# vacuum_gripper_v1.net
KiCad netlist of a schematic drawn in EAGLE
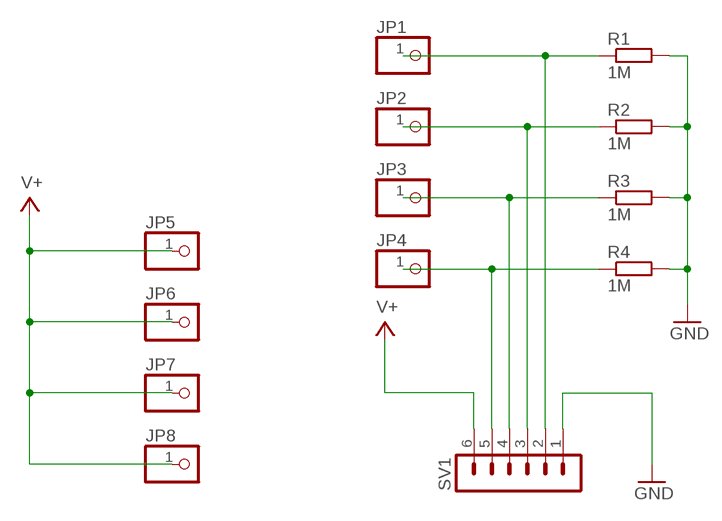
[diagram p0: schematic, sheet 1]

(export (version "E")
  (design (tool "Eeschema 10.0.6"))
  (components
    (comp (ref "JP1")
      (value "PINHD-1X1")
      (footprint "eagle-import:1X01")
      (libsource (lib "eagle-import") (part "PINHD-1X1"))
    )
    (comp (ref "JP2")
      (value "PINHD-1X1")
      (footprint "eagle-import:1X01")
      (libsource (lib "eagle-import") (part "PINHD-1X1"))
    )
    (comp (ref "JP3")
      (value "PINHD-1X1")
      (footprint "eagle-import:1X01")
      (libsource (lib "eagle-import") (part "PINHD-1X1"))
    )
    (comp (ref "JP4")
      (value "PINHD-1X1")
      (footprint "eagle-import:1X01")
      (libsource (lib "eagle-import") (part "PINHD-1X1"))
    )
    (comp (ref "JP5")
      (value "PINHD-1X1")
      (footprint "eagle-import:1X01")
      (libsource (lib "eagle-import") (part "PINHD-1X1"))
    )
    (comp (ref "JP6")
      (value "PINHD-1X1")
      (footprint "eagle-import:1X01")
      (libsource (lib "eagle-import") (part "PINHD-1X1"))
    )
    (comp (ref "JP7")
      (value "PINHD-1X1")
      (footprint "eagle-import:1X01")
      (libsource (lib "eagle-import") (part "PINHD-1X1"))
    )
    (comp (ref "JP8")
      (value "PINHD-1X1")
      (footprint "eagle-import:1X01")
      (libsource (lib "eagle-import") (part "PINHD-1X1"))
    )
    (comp (ref "R1")
      (value "1M")
      (footprint "eagle-import:R1206")
      (libsource (lib "eagle-import") (part "R-EU_R1206"))
    )
    (comp (ref "R2")
      (value "1M")
      (footprint "eagle-import:R1206")
      (libsource (lib "eagle-import") (part "R-EU_R1206"))
    )
    (comp (ref "R3")
      (value "1M")
      (footprint "eagle-import:R1206")
      (libsource (lib "eagle-import") (part "R-EU_R1206"))
    )
    (comp (ref "R4")
      (value "1M")
      (footprint "eagle-import:R1206")
      (libsource (lib "eagle-import") (part "R-EU_R1206"))
    )
    (comp (ref "SV1")
      (value "MA06-1")
      (footprint "eagle-import:MA06-1")
      (libsource (lib "eagle-import") (part "MA06-1"))
    )
  )
  (nets
    (net (code "1") (name "GND") (class "Default")
      (node (ref "R1") (pin "2") (pinfunction "2_2") (pintype "passive"))
      (node (ref "R2") (pin "2") (pinfunction "2_2") (pintype "passive"))
      (node (ref "R3") (pin "2") (pinfunction "2_2") (pintype "passive"))
      (node (ref "R4") (pin "2") (pinfunction "2_2") (pintype "passive"))
      (node (ref "SV1") (pin "1") (pinfunction "1_1") (pintype "passive"))
    )
    (net (code "2") (name "Net-(JP1-Pad1)") (class "Default")
      (node (ref "JP1") (pin "1") (pinfunction "1_1") (pintype "passive"))
      (node (ref "R1") (pin "1") (pinfunction "1_1") (pintype "passive"))
      (node (ref "SV1") (pin "2") (pinfunction "2_2") (pintype "passive"))
    )
    (net (code "3") (name "Net-(JP2-Pad1)") (class "Default")
      (node (ref "JP2") (pin "1") (pinfunction "1_1") (pintype "passive"))
      (node (ref "R2") (pin "1") (pinfunction "1_1") (pintype "passive"))
      (node (ref "SV1") (pin "3") (pinfunction "3_3") (pintype "passive"))
    )
    (net (code "4") (name "Net-(JP3-Pad1)") (class "Default")
      (node (ref "JP3") (pin "1") (pinfunction "1_1") (pintype "passive"))
      (node (ref "R3") (pin "1") (pinfunction "1_1") (pintype "passive"))
      (node (ref "SV1") (pin "4") (pinfunction "4_4") (pintype "passive"))
    )
    (net (code "5") (name "Net-(JP4-Pad1)") (class "Default")
      (node (ref "JP4") (pin "1") (pinfunction "1_1") (pintype "passive"))
      (node (ref "R4") (pin "1") (pinfunction "1_1") (pintype "passive"))
      (node (ref "SV1") (pin "5") (pinfunction "5_5") (pintype "passive"))
    )
    (net (code "6") (name "V+") (class "Default")
      (node (ref "JP5") (pin "1") (pinfunction "1_1") (pintype "passive"))
      (node (ref "JP6") (pin "1") (pinfunction "1_1") (pintype "passive"))
      (node (ref "JP7") (pin "1") (pinfunction "1_1") (pintype "passive"))
      (node (ref "JP8") (pin "1") (pinfunction "1_1") (pintype "passive"))
      (node (ref "SV1") (pin "6") (pinfunction "6_6") (pintype "passive"))
    )
  )
)
